# CT.net
KiCad netlist of a schematic drawn in Altium Designer
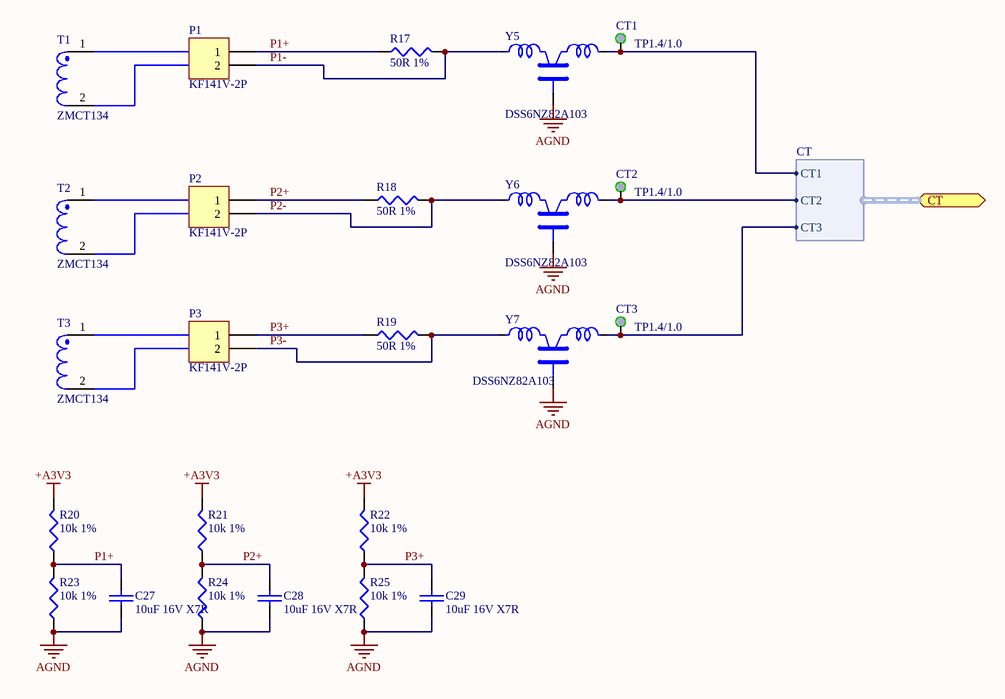
[diagram p0: CT.SchDoc]

(export (version "E")
  (design (tool "Eeschema 10.0.6"))
  (components
    (comp (ref "C27")
      (value "10uF 16V X7R")
      (footprint "IPC-7352 Chip_Capacitor_N:CAPC3216N")
      (libsource (lib "*") (part "CAP"))
    )
    (comp (ref "C28")
      (value "10uF 16V X7R")
      (footprint "IPC-7352 Chip_Capacitor_N:CAPC3216N")
      (libsource (lib "*") (part "CAP"))
    )
    (comp (ref "C29")
      (value "10uF 16V X7R")
      (footprint "IPC-7352 Chip_Capacitor_N:CAPC3216N")
      (libsource (lib "*") (part "CAP"))
    )
    (comp (ref "CT1")
      (value "TP1.4/1.0")
      (footprint "UserPcbLib:TP1.4/1.0")
      (libsource (lib "UserSchlib") (part "TP1.4/1.0"))
    )
    (comp (ref "CT2")
      (value "TP1.4/1.0")
      (footprint "UserPcbLib:TP1.4/1.0")
      (libsource (lib "UserSchlib") (part "TP1.4/1.0"))
    )
    (comp (ref "CT3")
      (value "TP1.4/1.0")
      (footprint "UserPcbLib:TP1.4/1.0")
      (libsource (lib "UserSchlib") (part "TP1.4/1.0"))
    )
    (comp (ref "P1")
      (value "KF141V-2P")
      (footprint "UserPcbLib:KF141V-2P")
      (description "CT connector")
      (fields (field (name "PUBLISHER") "Altium Limited"))
      (libsource (lib "Miscellaneous Connectors") (part "Header 2"))
    )
    (comp (ref "P2")
      (value "KF141V-2P")
      (footprint "UserPcbLib:KF141V-2P")
      (description "CT connector")
      (fields (field (name "PUBLISHER") "Altium Limited"))
      (libsource (lib "Miscellaneous Connectors") (part "Header 2"))
    )
    (comp (ref "P3")
      (value "KF141V-2P")
      (footprint "UserPcbLib:KF141V-2P")
      (description "CT connector")
      (fields (field (name "PUBLISHER") "Altium Limited"))
      (libsource (lib "Miscellaneous Connectors") (part "Header 2"))
    )
    (comp (ref "R17")
      (value "50R 1%")
      (footprint "IPC-7352 Chip_Resistor_N:RESC2012N")
      (description "Resistor")
      (fields (field (name "PUBLISHER") "Altium Limited"))
      (libsource (lib "Miscellaneous Devices") (part "Res3"))
    )
    (comp (ref "R18")
      (value "50R 1%")
      (footprint "IPC-7352 Chip_Resistor_N:RESC2012N")
      (description "Resistor")
      (fields (field (name "PUBLISHER") "Altium Limited"))
      (libsource (lib "Miscellaneous Devices") (part "Res3"))
    )
    (comp (ref "R19")
      (value "50R 1%")
      (footprint "IPC-7352 Chip_Resistor_N:RESC2012N")
      (description "Resistor")
      (fields (field (name "PUBLISHER") "Altium Limited"))
      (libsource (lib "Miscellaneous Devices") (part "Res3"))
    )
    (comp (ref "R20")
      (value "10k 1%")
      (footprint "IPC-7352 Chip_Resistor_N:RESC2012N")
      (description "Resistor")
      (fields (field (name "PUBLISHER") "Altium Limited"))
      (libsource (lib "Miscellaneous Devices") (part "Res3"))
    )
    (comp (ref "R21")
      (value "10k 1%")
      (footprint "IPC-7352 Chip_Resistor_N:RESC2012N")
      (description "Resistor")
      (fields (field (name "PUBLISHER") "Altium Limited"))
      (libsource (lib "Miscellaneous Devices") (part "Res3"))
    )
    (comp (ref "R22")
      (value "10k 1%")
      (footprint "IPC-7352 Chip_Resistor_N:RESC2012N")
      (description "Resistor")
      (fields (field (name "PUBLISHER") "Altium Limited"))
      (libsource (lib "Miscellaneous Devices") (part "Res3"))
    )
    (comp (ref "R23")
      (value "10k 1%")
      (footprint "IPC-7352 Chip_Resistor_N:RESC2012N")
      (description "Resistor")
      (fields (field (name "PUBLISHER") "Altium Limited"))
      (libsource (lib "Miscellaneous Devices") (part "Res3"))
    )
    (comp (ref "R24")
      (value "10k 1%")
      (footprint "IPC-7352 Chip_Resistor_N:RESC2012N")
      (description "Resistor")
      (fields (field (name "PUBLISHER") "Altium Limited"))
      (libsource (lib "Miscellaneous Devices") (part "Res3"))
    )
    (comp (ref "R25")
      (value "10k 1%")
      (footprint "IPC-7352 Chip_Resistor_N:RESC2012N")
      (description "Resistor")
      (fields (field (name "PUBLISHER") "Altium Limited"))
      (libsource (lib "Miscellaneous Devices") (part "Res3"))
    )
    (comp (ref "T1")
      (value "ZMCT134")
      (description "Current transformer")
      (libsource (lib "UserSchlib") (part "CURRENT_TRANS"))
    )
    (comp (ref "T2")
      (value "ZMCT134")
      (description "Current transformer")
      (libsource (lib "UserSchlib") (part "CURRENT_TRANS"))
    )
    (comp (ref "T3")
      (value "ZMCT134")
      (description "Current transformer")
      (libsource (lib "UserSchlib") (part "CURRENT_TRANS"))
    )
    (comp (ref "Y5")
      (value "DSS6NZ82A103")
      (footprint "UserPcbLib:DSS6")
      (description "Murata EMI suppression filter")
      (fields (field (name "MANUFACTURER") "Murata"))
      (libsource (lib "UserSchlib") (part "DSS6"))
    )
    (comp (ref "Y6")
      (value "DSS6NZ82A103")
      (footprint "UserPcbLib:DSS6")
      (description "Murata EMI suppression filter")
      (fields (field (name "MANUFACTURER") "Murata"))
      (libsource (lib "UserSchlib") (part "DSS6"))
    )
    (comp (ref "Y7")
      (value "DSS6NZ82A103")
      (footprint "UserPcbLib:DSS6")
      (description "Murata EMI suppression filter")
      (fields (field (name "MANUFACTURER") "Murata"))
      (libsource (lib "UserSchlib") (part "DSS6"))
    )
  )
  (nets
    (net (code "2") (name "+A3V3") (class "Default")
      (node (ref "R20") (pin "2") (pinfunction "2_2") (pintype "passive"))
      (node (ref "R21") (pin "2") (pinfunction "2_2") (pintype "passive"))
      (node (ref "R22") (pin "2") (pinfunction "2_2") (pintype "passive"))
    )
    (net (code "3") (name "/P1+") (class "Default")
      (node (ref "C27") (pin "2") (pintype "passive"))
      (node (ref "P1") (pin "1") (pinfunction "1_1") (pintype "passive"))
      (node (ref "R17") (pin "1") (pinfunction "1_1") (pintype "passive"))
      (node (ref "R20") (pin "1") (pinfunction "1_1") (pintype "passive"))
      (node (ref "R23") (pin "2") (pinfunction "2_2") (pintype "passive"))
    )
    (net (code "4") (name "/P1-") (class "Default")
      (node (ref "P1") (pin "2") (pinfunction "2_2") (pintype "passive"))
      (node (ref "R17") (pin "2") (pinfunction "2_2") (pintype "passive"))
      (node (ref "Y5") (pin "1") (pinfunction "1_1") (pintype "passive"))
    )
    (net (code "5") (name "/P2+") (class "Default")
      (node (ref "C28") (pin "2") (pintype "passive"))
      (node (ref "P2") (pin "1") (pinfunction "1_1") (pintype "passive"))
      (node (ref "R18") (pin "1") (pinfunction "1_1") (pintype "passive"))
      (node (ref "R21") (pin "1") (pinfunction "1_1") (pintype "passive"))
      (node (ref "R24") (pin "2") (pinfunction "2_2") (pintype "passive"))
    )
    (net (code "6") (name "/P2-") (class "Default")
      (node (ref "P2") (pin "2") (pinfunction "2_2") (pintype "passive"))
      (node (ref "R18") (pin "2") (pinfunction "2_2") (pintype "passive"))
      (node (ref "Y6") (pin "1") (pinfunction "1_1") (pintype "passive"))
    )
    (net (code "7") (name "/P3+") (class "Default")
      (node (ref "C29") (pin "2") (pintype "passive"))
      (node (ref "P3") (pin "1") (pinfunction "1_1") (pintype "passive"))
      (node (ref "R19") (pin "1") (pinfunction "1_1") (pintype "passive"))
      (node (ref "R22") (pin "1") (pinfunction "1_1") (pintype "passive"))
      (node (ref "R25") (pin "2") (pinfunction "2_2") (pintype "passive"))
    )
    (net (code "8") (name "/P3-") (class "Default")
      (node (ref "P3") (pin "2") (pinfunction "2_2") (pintype "passive"))
      (node (ref "R19") (pin "2") (pinfunction "2_2") (pintype "passive"))
      (node (ref "Y7") (pin "1") (pinfunction "1_1") (pintype "passive"))
    )
    (net (code "10") (name "AGND") (class "Default")
      (node (ref "C27") (pin "1") (pintype "passive"))
      (node (ref "C28") (pin "1") (pintype "passive"))
      (node (ref "C29") (pin "1") (pintype "passive"))
      (node (ref "R23") (pin "1") (pinfunction "1_1") (pintype "passive"))
      (node (ref "R24") (pin "1") (pinfunction "1_1") (pintype "passive"))
      (node (ref "R25") (pin "1") (pinfunction "1_1") (pintype "passive"))
      (node (ref "Y5") (pin "2") (pinfunction "2_2") (pintype "passive"))
      (node (ref "Y6") (pin "2") (pinfunction "2_2") (pintype "passive"))
      (node (ref "Y7") (pin "2") (pinfunction "2_2") (pintype "passive"))
    )
    (net (code "11") (name "Net-(CT1-Pad1)") (class "Default")
      (node (ref "CT1") (pin "1") (pinfunction "1_1") (pintype "passive"))
      (node (ref "Y5") (pin "3") (pinfunction "3_3") (pintype "passive"))
    )
    (net (code "12") (name "Net-(CT2-Pad1)") (class "Default")
      (node (ref "CT2") (pin "1") (pinfunction "1_1") (pintype "passive"))
      (node (ref "Y6") (pin "3") (pinfunction "3_3") (pintype "passive"))
    )
    (net (code "13") (name "Net-(CT3-Pad1)") (class "Default")
      (node (ref "CT3") (pin "1") (pinfunction "1_1") (pintype "passive"))
      (node (ref "Y7") (pin "3") (pinfunction "3_3") (pintype "passive"))
    )
    (net (code "14") (name "unconnected-(T1-Pad1)") (class "Default")
      (node (ref "T1") (pin "1") (pinfunction "1_1") (pintype "passive"))
    )
    (net (code "15") (name "unconnected-(T1-Pad2)") (class "Default")
      (node (ref "T1") (pin "2") (pinfunction "2_2") (pintype "passive"))
    )
    (net (code "16") (name "unconnected-(T2-Pad1)") (class "Default")
      (node (ref "T2") (pin "1") (pinfunction "1_1") (pintype "passive"))
    )
    (net (code "17") (name "unconnected-(T2-Pad2)") (class "Default")
      (node (ref "T2") (pin "2") (pinfunction "2_2") (pintype "passive"))
    )
    (net (code "18") (name "unconnected-(T3-Pad1)") (class "Default")
      (node (ref "T3") (pin "1") (pinfunction "1_1") (pintype "passive"))
    )
    (net (code "19") (name "unconnected-(T3-Pad2)") (class "Default")
      (node (ref "T3") (pin "2") (pinfunction "2_2") (pintype "passive"))
    )
  )
)
